# MotorAndRelayTest_v0_1_v1.net
KiCad netlist of a schematic drawn in EAGLE
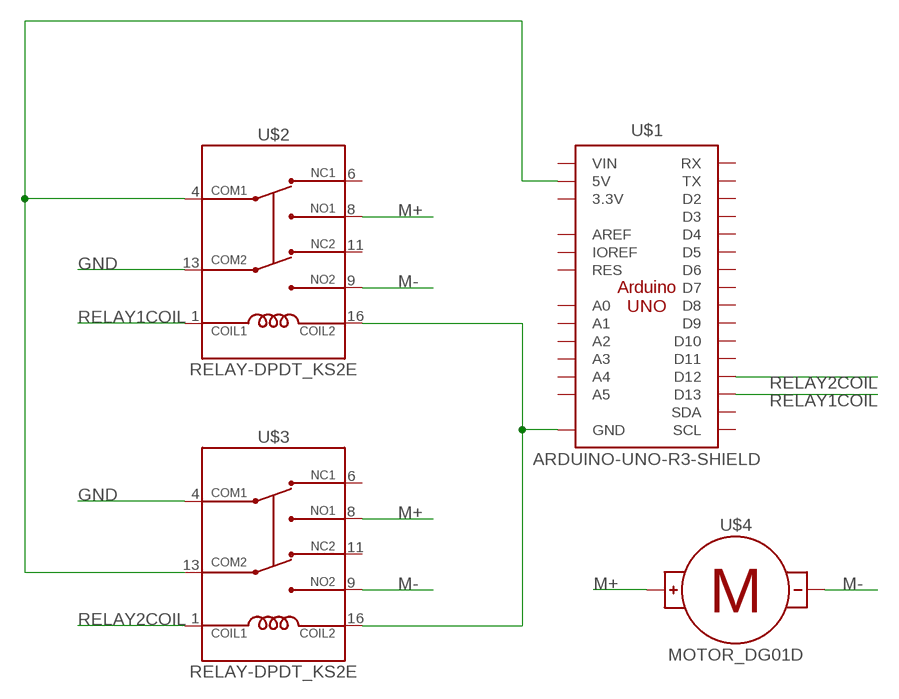
[diagram p0: schematic, sheet 1]

(export (version "E")
  (design (tool "Eeschema 10.0.6"))
  (components
    (comp (ref "U$1")
      (value "ARDUINO-UNO-R3-SHIELD")
      (footprint "eagle-import:ARDUINO-UNO-R3-SHIELD")
      (libsource (lib "eagle-import") (part "ARDUINO-UNO-R3-SHIELD"))
    )
    (comp (ref "U$2")
      (value "RELAY-DPDT_KS2E")
      (footprint "eagle-import:KS2E-M-DC5")
      (libsource (lib "eagle-import") (part "RELAY-DPDT_KS2E"))
    )
    (comp (ref "U$3")
      (value "RELAY-DPDT_KS2E")
      (footprint "eagle-import:KS2E-M-DC5")
      (libsource (lib "eagle-import") (part "RELAY-DPDT_KS2E"))
    )
    (comp (ref "U$4")
      (value "MOTOR_DG01D")
      (footprint "eagle-import:DG01D")
      (libsource (lib "eagle-import") (part "MOTOR_DG01D"))
    )
  )
  (nets
    (net (code "1") (name "/GND") (class "Default")
      (node (ref "U$2") (pin "13") (pinfunction "COM2_13") (pintype "bidirectional"))
      (node (ref "U$3") (pin "4") (pinfunction "COM1_4") (pintype "bidirectional"))
    )
    (net (code "2") (name "/M+") (class "Default")
      (node (ref "U$2") (pin "8") (pinfunction "NO1_8") (pintype "bidirectional"))
      (node (ref "U$3") (pin "8") (pinfunction "NO1_8") (pintype "bidirectional"))
      (node (ref "U$4") (pin "+") (pinfunction "+_+") (pintype "passive"))
    )
    (net (code "3") (name "/M-") (class "Default")
      (node (ref "U$2") (pin "9") (pinfunction "NO2_9") (pintype "bidirectional"))
      (node (ref "U$3") (pin "9") (pinfunction "NO2_9") (pintype "bidirectional"))
      (node (ref "U$4") (pin "-") (pinfunction "-_-") (pintype "passive"))
    )
    (net (code "4") (name "/RELAY1COIL") (class "Default")
      (node (ref "U$1") (pin "D13") (pinfunction "D13_D13") (pintype "bidirectional"))
      (node (ref "U$2") (pin "1") (pinfunction "COIL1_1") (pintype "bidirectional"))
    )
    (net (code "5") (name "/RELAY2COIL") (class "Default")
      (node (ref "U$1") (pin "D12") (pinfunction "D12_D12") (pintype "bidirectional"))
      (node (ref "U$3") (pin "1") (pinfunction "COIL1_1") (pintype "bidirectional"))
    )
    (net (code "6") (name "Net-(U$2-COIL2)") (class "Default")
      (node (ref "U$1") (pin "GND@0") (pinfunction "GND_GND@0") (pintype "bidirectional"))
      (node (ref "U$1") (pin "GND@1") (pinfunction "GND_GND@1") (pintype "bidirectional"))
      (node (ref "U$1") (pin "GND@2") (pinfunction "GND_GND@2") (pintype "bidirectional"))
      (node (ref "U$2") (pin "16") (pinfunction "COIL2_16") (pintype "bidirectional"))
      (node (ref "U$3") (pin "16") (pinfunction "COIL2_16") (pintype "bidirectional"))
    )
    (net (code "7") (name "Net-(U$2-COM1)") (class "Default")
      (node (ref "U$1") (pin "5V") (pinfunction "5V_5V") (pintype "bidirectional"))
      (node (ref "U$2") (pin "4") (pinfunction "COM1_4") (pintype "bidirectional"))
      (node (ref "U$3") (pin "13") (pinfunction "COM2_13") (pintype "bidirectional"))
    )
    (net (code "8") (name "unconnected-(U$1-Pad3.3V)") (class "Default")
      (node (ref "U$1") (pin "3.3V") (pinfunction "3.3V_3.3V") (pintype "bidirectional"))
    )
    (net (code "9") (name "unconnected-(U$1-PadA0)") (class "Default")
      (node (ref "U$1") (pin "A0") (pinfunction "A0_A0") (pintype "bidirectional"))
    )
    (net (code "10") (name "unconnected-(U$1-PadA1)") (class "Default")
      (node (ref "U$1") (pin "A1") (pinfunction "A1_A1") (pintype "bidirectional"))
    )
    (net (code "11") (name "unconnected-(U$1-PadA2)") (class "Default")
      (node (ref "U$1") (pin "A2") (pinfunction "A2_A2") (pintype "bidirectional"))
    )
    (net (code "12") (name "unconnected-(U$1-PadA3)") (class "Default")
      (node (ref "U$1") (pin "A3") (pinfunction "A3_A3") (pintype "bidirectional"))
    )
    (net (code "13") (name "unconnected-(U$1-PadA4)") (class "Default")
      (node (ref "U$1") (pin "A4") (pinfunction "A4_A4") (pintype "bidirectional"))
    )
    (net (code "14") (name "unconnected-(U$1-PadA5)") (class "Default")
      (node (ref "U$1") (pin "A5") (pinfunction "A5_A5") (pintype "bidirectional"))
    )
    (net (code "15") (name "unconnected-(U$1-PadAREF)") (class "Default")
      (node (ref "U$1") (pin "AREF") (pinfunction "AREF_AREF") (pintype "bidirectional"))
    )
    (net (code "16") (name "unconnected-(U$1-PadD2)") (class "Default")
      (node (ref "U$1") (pin "D2") (pinfunction "D2_D2") (pintype "bidirectional"))
    )
    (net (code "17") (name "unconnected-(U$1-PadD3)") (class "Default")
      (node (ref "U$1") (pin "D3") (pinfunction "D3_D3") (pintype "bidirectional"))
    )
    (net (code "18") (name "unconnected-(U$1-PadD4)") (class "Default")
      (node (ref "U$1") (pin "D4") (pinfunction "D4_D4") (pintype "bidirectional"))
    )
    (net (code "19") (name "unconnected-(U$1-PadD5)") (class "Default")
      (node (ref "U$1") (pin "D5") (pinfunction "D5_D5") (pintype "bidirectional"))
    )
    (net (code "20") (name "unconnected-(U$1-PadD6)") (class "Default")
      (node (ref "U$1") (pin "D6") (pinfunction "D6_D6") (pintype "bidirectional"))
    )
    (net (code "21") (name "unconnected-(U$1-PadD7)") (class "Default")
      (node (ref "U$1") (pin "D7") (pinfunction "D7_D7") (pintype "bidirectional"))
    )
    (net (code "22") (name "unconnected-(U$1-PadD8)") (class "Default")
      (node (ref "U$1") (pin "D8") (pinfunction "D8_D8") (pintype "bidirectional"))
    )
    (net (code "23") (name "unconnected-(U$1-PadD9)") (class "Default")
      (node (ref "U$1") (pin "D9") (pinfunction "D9_D9") (pintype "bidirectional"))
    )
    (net (code "24") (name "unconnected-(U$1-PadD10)") (class "Default")
      (node (ref "U$1") (pin "D10") (pinfunction "D10_D10") (pintype "bidirectional"))
    )
    (net (code "25") (name "unconnected-(U$1-PadD11)") (class "Default")
      (node (ref "U$1") (pin "D11") (pinfunction "D11_D11") (pintype "bidirectional"))
    )
    (net (code "26") (name "unconnected-(U$1-PadIOREF)") (class "Default")
      (node (ref "U$1") (pin "IOREF") (pinfunction "IOREF_IOREF") (pintype "bidirectional"))
    )
    (net (code "27") (name "unconnected-(U$1-PadRES)") (class "Default")
      (node (ref "U$1") (pin "RES") (pinfunction "RES_RES") (pintype "bidirectional"))
    )
    (net (code "28") (name "unconnected-(U$1-PadRX)") (class "Default")
      (node (ref "U$1") (pin "RX") (pinfunction "RX_RX") (pintype "bidirectional"))
    )
    (net (code "29") (name "unconnected-(U$1-PadSCL)") (class "Default")
      (node (ref "U$1") (pin "SCL") (pinfunction "SCL_SCL") (pintype "bidirectional"))
    )
    (net (code "30") (name "unconnected-(U$1-PadSDA)") (class "Default")
      (node (ref "U$1") (pin "SDA") (pinfunction "SDA_SDA") (pintype "bidirectional"))
    )
    (net (code "31") (name "unconnected-(U$1-PadTX)") (class "Default")
      (node (ref "U$1") (pin "TX") (pinfunction "TX_TX") (pintype "bidirectional"))
    )
    (net (code "32") (name "unconnected-(U$1-PadVIN)") (class "Default")
      (node (ref "U$1") (pin "VIN") (pinfunction "VIN_VIN") (pintype "bidirectional"))
    )
    (net (code "33") (name "unconnected-(U$2-NC1-Pad6)") (class "Default")
      (node (ref "U$2") (pin "6") (pinfunction "NC1_6") (pintype "bidirectional"))
    )
    (net (code "34") (name "unconnected-(U$2-NC2-Pad11)") (class "Default")
      (node (ref "U$2") (pin "11") (pinfunction "NC2_11") (pintype "bidirectional"))
    )
    (net (code "35") (name "unconnected-(U$3-NC1-Pad6)") (class "Default")
      (node (ref "U$3") (pin "6") (pinfunction "NC1_6") (pintype "bidirectional"))
    )
    (net (code "36") (name "unconnected-(U$3-NC2-Pad11)") (class "Default")
      (node (ref "U$3") (pin "11") (pinfunction "NC2_11") (pintype "bidirectional"))
    )
  )
)
